# E17-12-VCU-CONN.net
KiCad netlist of a schematic drawn in Altium Designer
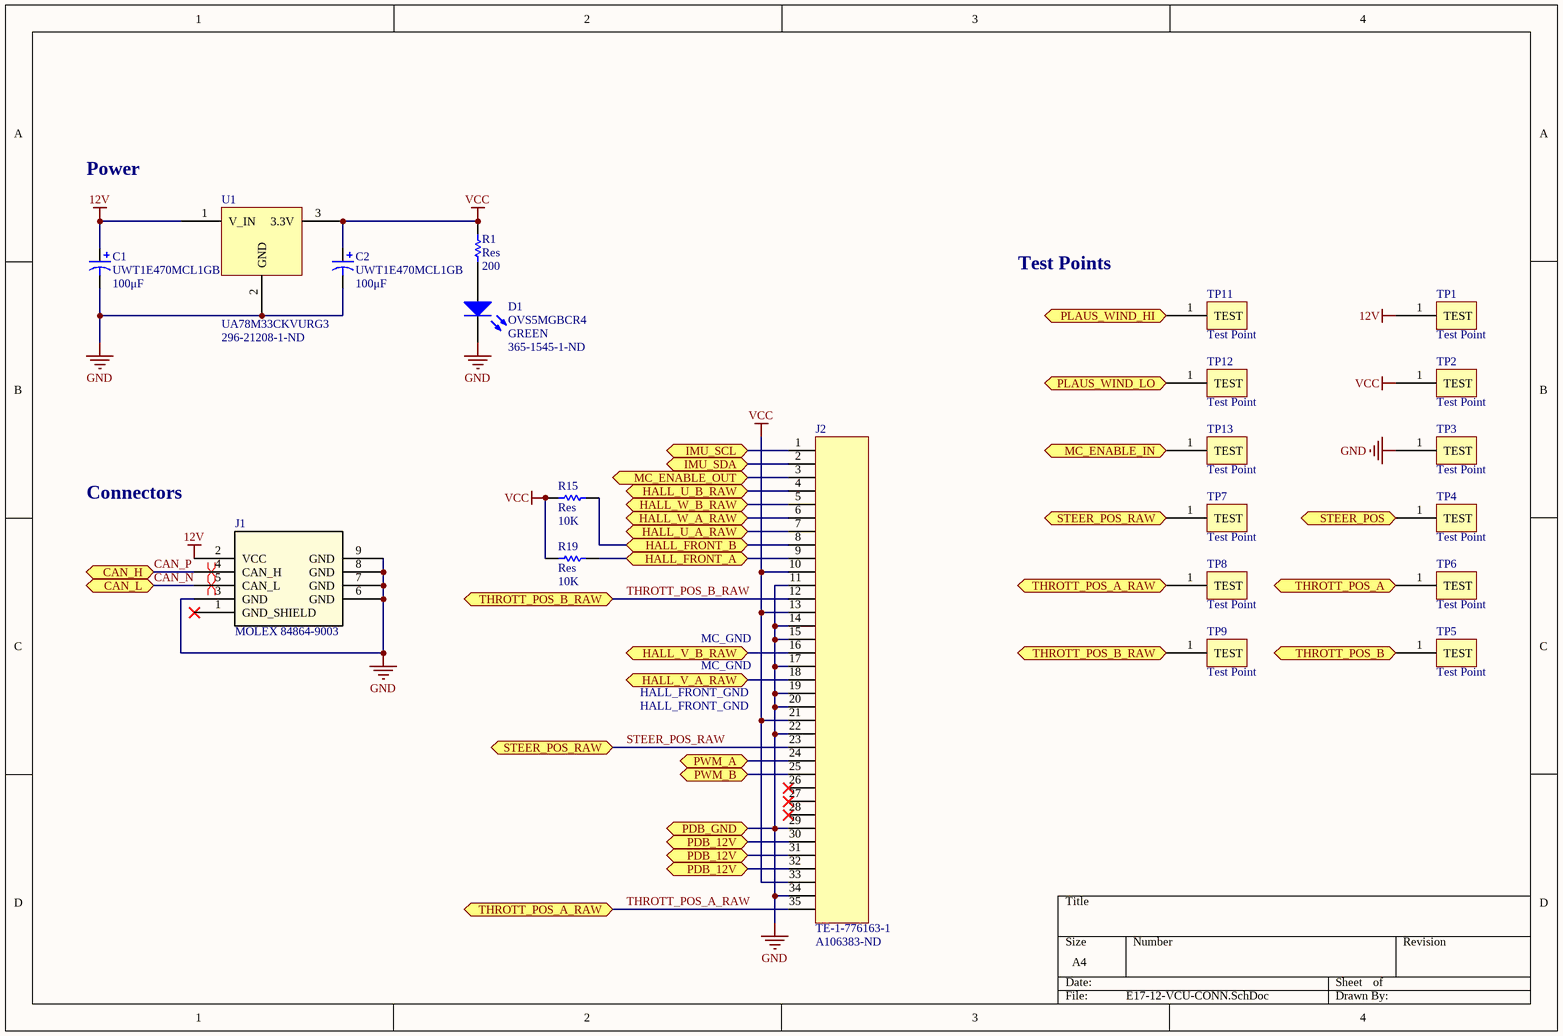
[diagram p0: E17-12-VCU-CONN.SchDoc]

(export (version "E")
  (design (tool "Eeschema 10.0.6"))
  (components
    (comp (ref "C1")
      (value "UWT1E470MCL1GB")
      (footprint "UWT1E470MCL1GB")
      (description "CAP ALUM 47UF 25V 20% SMD")
      (fields (field (name "ALTIUM_VALUE") "100μF") (field (name "PUBLISHER") "Altium Limited"))
      (libsource (lib "Capacitors") (part "UWT1E470MCL1GB"))
    )
    (comp (ref "C2")
      (value "UWT1E470MCL1GB")
      (footprint "UWT1E470MCL1GB")
      (description "CAP ALUM 47UF 25V 20% SMD")
      (fields (field (name "ALTIUM_VALUE") "100μF") (field (name "PUBLISHER") "Altium Limited"))
      (libsource (lib "Capacitors") (part "UWT1E470MCL1GB"))
    )
    (comp (ref "D1")
      (value "OVS5MGBCR4")
      (footprint "OVS5MGBCR4")
      (description "Typical GREEN LED")
      (fields
        (field (name "COLOUR") "GREEN")
        (field (name "SUPPLIER PART NUMBER 1") "365-1545-1-ND")
        (field (name "PUBLISHER") "Altium Limited")
      )
      (libsource (lib "LEDs") (part "OVS5MGBCR4"))
    )
    (comp (ref "J1")
      (value "MOLEX 84864-9003")
      (footprint "MOLEX 84864-9003")
      (description "CAN Micro-Change M12, Right Angle, Male")
      (libsource (lib "Connectors and Headers") (part "MOLEX 84864-9003"))
    )
    (comp (ref "J2")
      (value "TE-1-776163-1")
      (footprint "TE-1-776163-1")
      (description "CONN HEADER 35POS R/A GOLD BLACK")
      (fields (field (name "SUPPLIER PART NUMBER 1") "A106383-ND"))
      (libsource (lib "Connectors and Headers") (part "TE-1-776163-1"))
    )
    (comp (ref "R1")
      (value "Res")
      (footprint "2012[0805]")
      (description "Surface Mount Resistor")
      (fields (field (name "ALTIUM_VALUE") "200") (field (name "PUBLISHER") "Altium Limited"))
      (libsource (lib "Resistors") (part "Res"))
    )
    (comp (ref "R15")
      (value "Res")
      (footprint "2012[0805]")
      (description "Surface Mount Resistor")
      (fields (field (name "ALTIUM_VALUE") "10K") (field (name "PUBLISHER") "Altium Limited"))
      (libsource (lib "Resistors") (part "Res"))
    )
    (comp (ref "R19")
      (value "Res")
      (footprint "2012[0805]")
      (description "Surface Mount Resistor")
      (fields (field (name "ALTIUM_VALUE") "10K") (field (name "PUBLISHER") "Altium Limited"))
      (libsource (lib "Resistors") (part "Res"))
    )
    (comp (ref "TP1")
      (value "Test Point")
      (footprint "TEST POINT 5000K")
      (description "5000-5004, 5015-5019 Keystone Electronics")
      (libsource (lib "Mechanical Devices") (part "Test Point"))
    )
    (comp (ref "TP2")
      (value "Test Point")
      (footprint "TEST POINT 5000K")
      (description "5000-5004, 5015-5019 Keystone Electronics")
      (libsource (lib "Mechanical Devices") (part "Test Point"))
    )
    (comp (ref "TP3")
      (value "Test Point")
      (footprint "TEST POINT 5000K")
      (description "5000-5004, 5015-5019 Keystone Electronics")
      (libsource (lib "Mechanical Devices") (part "Test Point"))
    )
    (comp (ref "TP4")
      (value "Test Point")
      (footprint "TEST POINT 5000K")
      (description "5000-5004, 5015-5019 Keystone Electronics")
      (libsource (lib "Mechanical Devices") (part "Test Point"))
    )
    (comp (ref "TP5")
      (value "Test Point")
      (footprint "TEST POINT 5000K")
      (description "5000-5004, 5015-5019 Keystone Electronics")
      (libsource (lib "Mechanical Devices") (part "Test Point"))
    )
    (comp (ref "TP6")
      (value "Test Point")
      (footprint "TEST POINT 5000K")
      (description "5000-5004, 5015-5019 Keystone Electronics")
      (libsource (lib "Mechanical Devices") (part "Test Point"))
    )
    (comp (ref "TP7")
      (value "Test Point")
      (footprint "TEST POINT 5000K")
      (description "5000-5004, 5015-5019 Keystone Electronics")
      (libsource (lib "Mechanical Devices") (part "Test Point"))
    )
    (comp (ref "TP8")
      (value "Test Point")
      (footprint "TEST POINT 5000K")
      (description "5000-5004, 5015-5019 Keystone Electronics")
      (libsource (lib "Mechanical Devices") (part "Test Point"))
    )
    (comp (ref "TP9")
      (value "Test Point")
      (footprint "TEST POINT 5000K")
      (description "5000-5004, 5015-5019 Keystone Electronics")
      (libsource (lib "Mechanical Devices") (part "Test Point"))
    )
    (comp (ref "TP11")
      (value "Test Point")
      (footprint "TEST POINT 5000K")
      (description "5000-5004, 5015-5019 Keystone Electronics")
      (libsource (lib "Mechanical Devices") (part "Test Point"))
    )
    (comp (ref "TP12")
      (value "Test Point")
      (footprint "TEST POINT 5000K")
      (description "5000-5004, 5015-5019 Keystone Electronics")
      (libsource (lib "Mechanical Devices") (part "Test Point"))
    )
    (comp (ref "TP13")
      (value "Test Point")
      (footprint "TEST POINT 5000K")
      (description "5000-5004, 5015-5019 Keystone Electronics")
      (libsource (lib "Mechanical Devices") (part "Test Point"))
    )
    (comp (ref "U1")
      (value "UA78M33CKVURG3")
      (footprint "TO-252-3")
      (description "3.3V Regulator")
      (fields (field (name "SUPPLIER PART NUMBER 1") "296-21208-1-ND"))
      (libsource (lib "Voltage Regulation") (part "UA78M33CKVURG3"))
    )
  )
  (nets
    (net (code "1") (name "/CAN_N") (class "Default")
      (node (ref "J1") (pin "5") (pinfunction "CAN_L_5") (pintype "passive"))
    )
    (net (code "2") (name "/CAN_P") (class "Default")
      (node (ref "J1") (pin "4") (pinfunction "CAN_H_4") (pintype "passive"))
    )
    (net (code "3") (name "/HALL_FRONT_A") (class "Default")
      (node (ref "J2") (pin "9") (pintype "passive"))
      (node (ref "R19") (pin "1") (pinfunction "1_1") (pintype "passive"))
    )
    (net (code "4") (name "/HALL_FRONT_B") (class "Default")
      (node (ref "J2") (pin "8") (pintype "passive"))
      (node (ref "R15") (pin "2") (pinfunction "2_2") (pintype "passive"))
    )
    (net (code "5") (name "/HALL_U_A_RAW") (class "Default") (node (ref "J2") (pin "7") (pintype "passive")))
    (net (code "6") (name "/HALL_U_B_RAW") (class "Default") (node (ref "J2") (pin "4") (pintype "passive")))
    (net (code "7") (name "/HALL_V_A_RAW") (class "Default") (node (ref "J2") (pin "18") (pintype "passive")))
    (net (code "8") (name "/HALL_V_B_RAW") (class "Default") (node (ref "J2") (pin "16") (pintype "passive")))
    (net (code "9") (name "/HALL_W_A_RAW") (class "Default") (node (ref "J2") (pin "6") (pintype "passive")))
    (net (code "10") (name "/HALL_W_B_RAW") (class "Default") (node (ref "J2") (pin "5") (pintype "passive")))
    (net (code "11") (name "/IMU_SCL") (class "Default") (node (ref "J2") (pin "1") (pintype "passive")))
    (net (code "12") (name "/IMU_SDA") (class "Default") (node (ref "J2") (pin "2") (pintype "passive")))
    (net (code "13") (name "/MC_ENABLE_IN") (class "Default")
      (node (ref "TP13") (pin "1") (pinfunction "TEST_1") (pintype "passive"))
    )
    (net (code "14") (name "/MC_ENABLE_OUT") (class "Default")
      (node (ref "J2") (pin "3") (pintype "passive"))
    )
    (net (code "15") (name "/PDB_12V") (class "Default")
      (node (ref "J2") (pin "30") (pintype "passive"))
      (node (ref "J2") (pin "31") (pintype "passive"))
      (node (ref "J2") (pin "32") (pintype "passive"))
    )
    (net (code "16") (name "/PLAUS_WIND_HI") (class "Default")
      (node (ref "TP11") (pin "1") (pinfunction "TEST_1") (pintype "passive"))
    )
    (net (code "17") (name "/PLAUS_WIND_LO") (class "Default")
      (node (ref "TP12") (pin "1") (pinfunction "TEST_1") (pintype "passive"))
    )
    (net (code "18") (name "/PWM_A") (class "Default") (node (ref "J2") (pin "24") (pintype "passive")))
    (net (code "19") (name "/PWM_B") (class "Default") (node (ref "J2") (pin "25") (pintype "passive")))
    (net (code "20") (name "/STEER_POS") (class "Default")
      (node (ref "TP4") (pin "1") (pinfunction "TEST_1") (pintype "passive"))
    )
    (net (code "21") (name "/STEER_POS_RAW") (class "Default")
      (node (ref "J2") (pin "23") (pintype "passive"))
      (node (ref "TP7") (pin "1") (pinfunction "TEST_1") (pintype "passive"))
    )
    (net (code "22") (name "/THROTT_POS_A") (class "Default")
      (node (ref "TP6") (pin "1") (pinfunction "TEST_1") (pintype "passive"))
    )
    (net (code "23") (name "/THROTT_POS_A_RAW") (class "Default")
      (node (ref "J2") (pin "35") (pintype "passive"))
      (node (ref "TP8") (pin "1") (pinfunction "TEST_1") (pintype "passive"))
    )
    (net (code "24") (name "/THROTT_POS_B") (class "Default")
      (node (ref "TP5") (pin "1") (pinfunction "TEST_1") (pintype "passive"))
    )
    (net (code "25") (name "/THROTT_POS_B_RAW") (class "Default")
      (node (ref "J2") (pin "12") (pintype "passive"))
      (node (ref "TP9") (pin "1") (pinfunction "TEST_1") (pintype "passive"))
    )
    (net (code "26") (name "12V") (class "Default")
      (node (ref "C1") (pin "1") (pinfunction "1_1") (pintype "passive"))
      (node (ref "J1") (pin "2") (pinfunction "VCC_2") (pintype "passive"))
      (node (ref "TP1") (pin "1") (pinfunction "TEST_1") (pintype "passive"))
      (node (ref "U1") (pin "1") (pinfunction "V_IN_1") (pintype "passive"))
    )
    (net (code "27") (name "GND") (class "Default")
      (node (ref "C1") (pin "2") (pinfunction "2_2") (pintype "passive"))
      (node (ref "C2") (pin "2") (pinfunction "2_2") (pintype "passive"))
      (node (ref "D1") (pin "2") (pinfunction "K_2") (pintype "passive"))
      (node (ref "J1") (pin "3") (pinfunction "GND_3") (pintype "passive"))
      (node (ref "J1") (pin "6") (pinfunction "GND_6") (pintype "passive"))
      (node (ref "J1") (pin "7") (pinfunction "GND_7") (pintype "passive"))
      (node (ref "J1") (pin "8") (pinfunction "GND_8") (pintype "passive"))
      (node (ref "J1") (pin "9") (pinfunction "GND_9") (pintype "passive"))
      (node (ref "J2") (pin "11") (pintype "passive"))
      (node (ref "J2") (pin "14") (pintype "passive"))
      (node (ref "J2") (pin "15") (pintype "passive"))
      (node (ref "J2") (pin "17") (pintype "passive"))
      (node (ref "J2") (pin "19") (pintype "passive"))
      (node (ref "J2") (pin "20") (pintype "passive"))
      (node (ref "J2") (pin "22") (pintype "passive"))
      (node (ref "J2") (pin "29") (pintype "passive"))
      (node (ref "J2") (pin "34") (pintype "passive"))
      (node (ref "TP3") (pin "1") (pinfunction "TEST_1") (pintype "passive"))
      (node (ref "U1") (pin "2") (pinfunction "GND_2") (pintype "passive"))
    )
    (net (code "28") (name "Net-(D1-A)") (class "Default")
      (node (ref "D1") (pin "1") (pinfunction "A_1") (pintype "passive"))
      (node (ref "R1") (pin "1") (pinfunction "1_1") (pintype "passive"))
    )
    (net (code "29") (name "VCC") (class "Default")
      (node (ref "C2") (pin "1") (pinfunction "1_1") (pintype "passive"))
      (node (ref "J2") (pin "10") (pintype "passive"))
      (node (ref "J2") (pin "13") (pintype "passive"))
      (node (ref "J2") (pin "21") (pintype "passive"))
      (node (ref "J2") (pin "33") (pintype "passive"))
      (node (ref "R1") (pin "2") (pinfunction "2_2") (pintype "passive"))
      (node (ref "R15") (pin "1") (pinfunction "1_1") (pintype "passive"))
      (node (ref "R19") (pin "2") (pinfunction "2_2") (pintype "passive"))
      (node (ref "TP2") (pin "1") (pinfunction "TEST_1") (pintype "passive"))
      (node (ref "U1") (pin "3") (pinfunction "3.3V_3") (pintype "passive"))
    )
    (net (code "30") (name "unconnected-(J1-GND_SHIELD-Pad1)") (class "Default")
      (node (ref "J1") (pin "1") (pinfunction "GND_SHIELD_1") (pintype "passive+no_connect"))
    )
    (net (code "31") (name "unconnected-(J2-Pad26)") (class "Default")
      (node (ref "J2") (pin "26") (pintype "passive+no_connect"))
    )
    (net (code "32") (name "unconnected-(J2-Pad27)") (class "Default")
      (node (ref "J2") (pin "27") (pintype "passive+no_connect"))
    )
    (net (code "33") (name "unconnected-(J2-Pad28)") (class "Default")
      (node (ref "J2") (pin "28") (pintype "passive+no_connect"))
    )
  )
)
